# TI_92_power.net
KiCad netlist of a schematic drawn in Altium Designer
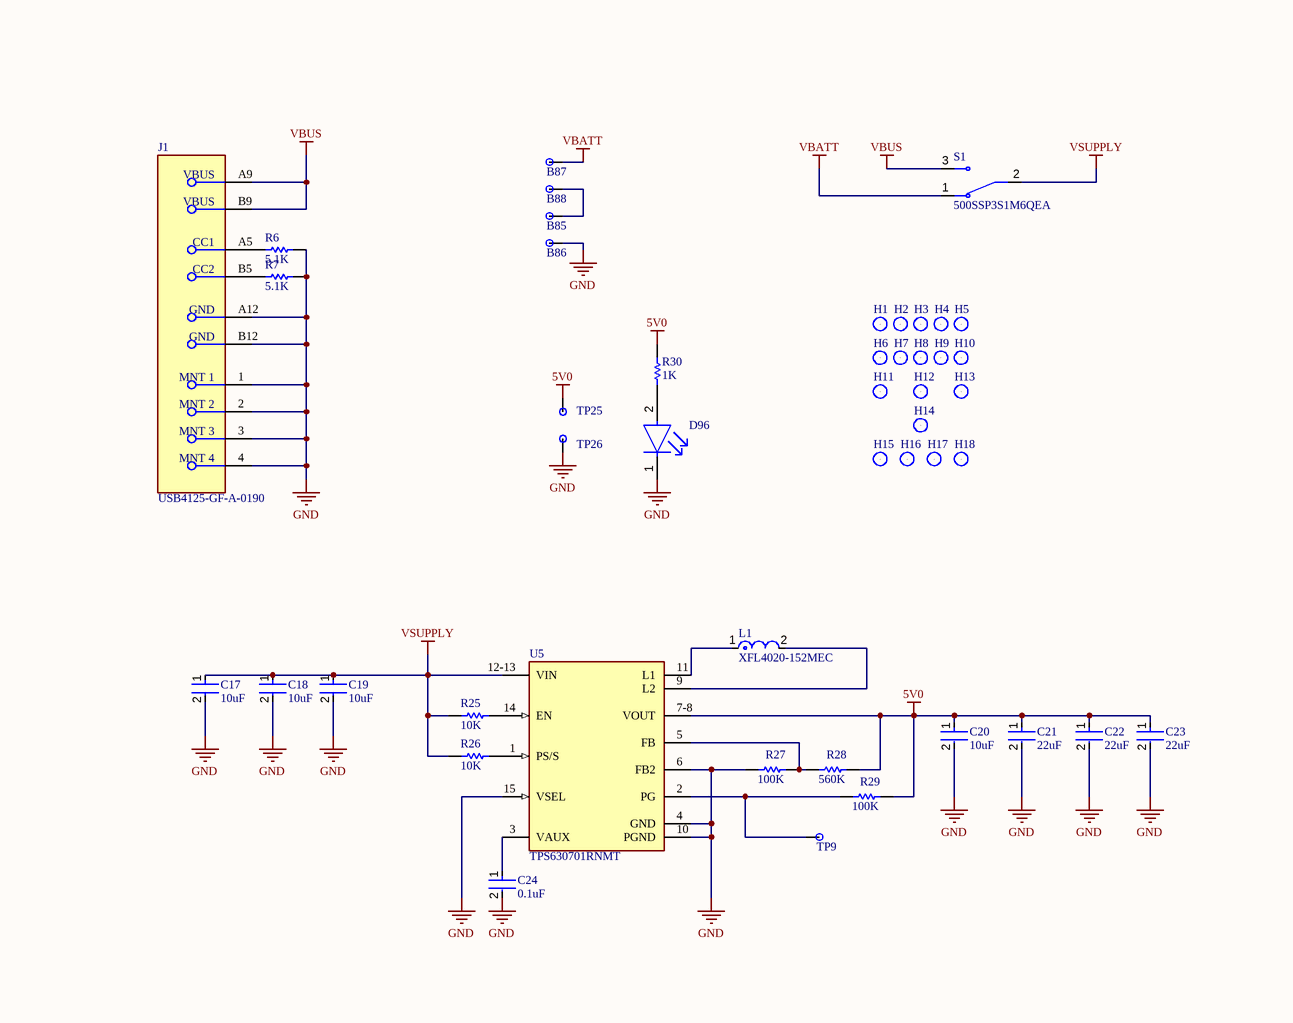
[diagram p0: TI_92_power.SchDoc]

(export (version "E")
  (design (tool "Eeschema 10.0.6"))
  (components
    (comp (ref "B85")
      (value "Test Pad")
      (footprint "10mm_x_10mm_PAD")
      (description "Various Test Pads")
      (libsource (lib "TI_kbd") (part "Test_Pad"))
    )
    (comp (ref "B86")
      (value "Test Pad")
      (footprint "10mm_x_8mm_PAD")
      (description "Various Test Pads")
      (libsource (lib "TI_kbd") (part "Test_Pad"))
    )
    (comp (ref "B87")
      (value "Test Pad")
      (footprint "10mm_x_10mm_PAD")
      (description "Various Test Pads")
      (libsource (lib "TI_kbd") (part "Test_Pad"))
    )
    (comp (ref "B88")
      (value "Test Pad")
      (footprint "10mm_x_8mm_PAD")
      (description "Various Test Pads")
      (libsource (lib "TI_kbd") (part "Test_Pad"))
    )
    (comp (ref "C17")
      (value "10uF")
      (footprint "FP-GRM21B-0_2-e0_2_0_7-IPC_A")
      (description "Chip Multilayer Ceramic Capacitors for General Purpose, 0805, 10uF, X7S, 22%, 20%, 25V")
      (fields (field (name "TOLERANCE") "20%"))
      (libsource (lib "Altium Content Vault") (part "b4654b650e69147ec39a6b967a45e02"))
    )
    (comp (ref "C18")
      (value "10uF")
      (footprint "FP-GRM21B-0_2-e0_2_0_7-IPC_A")
      (description "Chip Multilayer Ceramic Capacitors for General Purpose, 0805, 10uF, X7S, 22%, 20%, 25V")
      (fields (field (name "TOLERANCE") "20%"))
      (libsource (lib "Altium Content Vault") (part "b4654b650e69147ec39a6b967a45e02"))
    )
    (comp (ref "C19")
      (value "10uF")
      (footprint "FP-0603-L_1_6_0_2-W_0_8_0-MFG")
      (description "Multilayer Ceramic Capacitor 10uF 25V X5R 20% SMD 0603 T/R")
      (fields (field (name "TOLERANCE") "20%"))
      (libsource (lib "Altium Content Vault") (part "b4654b650e69147ec39a6b967a45e02"))
    )
    (comp (ref "C20")
      (value "10uF")
      (footprint "FP-0603-L_1_6_0_2-W_0_8_0-MFG")
      (description "Multilayer Ceramic Capacitor 10uF 25V X5R 20% SMD 0603 T/R")
      (fields (field (name "TOLERANCE") "20%"))
      (libsource (lib "Altium Content Vault") (part "b4654b650e69147ec39a6b967a45e02"))
    )
    (comp (ref "C21")
      (value "22uF")
      (footprint "FP-GRM21B-0_2-e0_2_0_7-MFG")
      (description "Chip Multilayer Ceramic Capacitors for General Purpose, 0805, 22uF, X6S, 22%, 20%, 16V")
      (fields (field (name "TOLERANCE") "20%"))
      (libsource (lib "Altium Content Vault") (part "b4654b650e69147ec39a6b967a45e02"))
    )
    (comp (ref "C22")
      (value "22uF")
      (footprint "FP-GRM21B-0_2-e0_2_0_7-MFG")
      (description "Chip Multilayer Ceramic Capacitors for General Purpose, 0805, 22uF, X6S, 22%, 20%, 16V")
      (fields (field (name "TOLERANCE") "20%"))
      (libsource (lib "Altium Content Vault") (part "b4654b650e69147ec39a6b967a45e02"))
    )
    (comp (ref "C23")
      (value "22uF")
      (footprint "FP-GRM21B-0_2-e0_2_0_7-MFG")
      (description "Chip Multilayer Ceramic Capacitors for General Purpose, 0805, 22uF, X6S, 22%, 20%, 16V")
      (fields (field (name "TOLERANCE") "20%"))
      (libsource (lib "Altium Content Vault") (part "b4654b650e69147ec39a6b967a45e02"))
    )
    (comp (ref "C24")
      (value "0.1uF")
      (footprint "FP-0402-L_1_0_0_05-W_0_5-IPC_B")
      (description "None")
      (fields (field (name "TOLERANCE") "20%"))
      (libsource (lib "Altium Content Vault") (part "b4654b650e69147ec39a6b967a45e02"))
    )
    (comp (ref "D96")
      (value "APHHS1005CGCK")
      (footprint "FP-APHHS1005CGCK-MFG")
      (description "LED GREEN CLEAR CHIP SMD")
      (libsource (lib "Altium Content Vault") (part "8706943c75ba83719d021d2fdc84c58"))
    )
    (comp (ref "H1")
      (value "Mounting Hole")
      (footprint "2.7mm_HOLE")
      (description "Various Mounting Holes")
      (libsource (lib "TI_kbd") (part "Mounting_Hole"))
    )
    (comp (ref "H2")
      (value "Mounting Hole")
      (footprint "2.7mm_HOLE")
      (description "Various Mounting Holes")
      (libsource (lib "TI_kbd") (part "Mounting_Hole"))
    )
    (comp (ref "H3")
      (value "Mounting Hole")
      (footprint "1.5mm_hole")
      (description "Various Mounting Holes")
      (libsource (lib "TI_kbd") (part "Mounting_Hole"))
    )
    (comp (ref "H4")
      (value "Mounting Hole")
      (footprint "2.7mm_HOLE")
      (description "Various Mounting Holes")
      (libsource (lib "TI_kbd") (part "Mounting_Hole"))
    )
    (comp (ref "H5")
      (value "Mounting Hole")
      (footprint "2.7mm_HOLE")
      (description "Various Mounting Holes")
      (libsource (lib "TI_kbd") (part "Mounting_Hole"))
    )
    (comp (ref "H6")
      (value "Mounting Hole")
      (footprint "2.7mm_HOLE")
      (description "Various Mounting Holes")
      (libsource (lib "TI_kbd") (part "Mounting_Hole"))
    )
    (comp (ref "H7")
      (value "Mounting Hole")
      (footprint "2.7mm_HOLE")
      (description "Various Mounting Holes")
      (libsource (lib "TI_kbd") (part "Mounting_Hole"))
    )
    (comp (ref "H8")
      (value "Mounting Hole")
      (footprint "2.7mm_HOLE")
      (description "Various Mounting Holes")
      (libsource (lib "TI_kbd") (part "Mounting_Hole"))
    )
    (comp (ref "H9")
      (value "Mounting Hole")
      (footprint "2.7mm_HOLE")
      (description "Various Mounting Holes")
      (libsource (lib "TI_kbd") (part "Mounting_Hole"))
    )
    (comp (ref "H10")
      (value "Mounting Hole")
      (footprint "2.7mm_HOLE")
      (description "Various Mounting Holes")
      (libsource (lib "TI_kbd") (part "Mounting_Hole"))
    )
    (comp (ref "H11")
      (value "Mounting Hole")
      (footprint "2.4mm_HOLE")
      (description "Various Mounting Holes")
      (libsource (lib "TI_kbd") (part "Mounting_Hole"))
    )
    (comp (ref "H12")
      (value "Mounting Hole")
      (footprint "2.4mm_HOLE")
      (description "Various Mounting Holes")
      (libsource (lib "TI_kbd") (part "Mounting_Hole"))
    )
    (comp (ref "H13")
      (value "Mounting Hole")
      (footprint "2.4mm_HOLE")
      (description "Various Mounting Holes")
      (libsource (lib "TI_kbd") (part "Mounting_Hole"))
    )
    (comp (ref "H14")
      (value "Mounting Hole")
      (footprint "1.5mm_hole")
      (description "Various Mounting Holes")
      (libsource (lib "TI_kbd") (part "Mounting_Hole"))
    )
    (comp (ref "H15")
      (value "Mounting Hole")
      (footprint "3.1mm_HOLE")
      (description "Various Mounting Holes")
      (libsource (lib "TI_kbd") (part "Mounting_Hole"))
    )
    (comp (ref "H16")
      (value "Mounting Hole")
      (footprint "3.1mm_HOLE")
      (description "Various Mounting Holes")
      (libsource (lib "TI_kbd") (part "Mounting_Hole"))
    )
    (comp (ref "H17")
      (value "Mounting Hole")
      (footprint "3.1mm_HOLE")
      (description "Various Mounting Holes")
      (libsource (lib "TI_kbd") (part "Mounting_Hole"))
    )
    (comp (ref "H18")
      (value "Mounting Hole")
      (footprint "3.1mm_HOLE")
      (description "Various Mounting Holes")
      (libsource (lib "TI_kbd") (part "Mounting_Hole"))
    )
    (comp (ref "J1")
      (value "USB4125-GF-A-0190")
      (footprint "FP-USB4125-GF-A-0190-MFG")
      (description "CONN RCPT TYPE C 6P SMD RA")
      (libsource (lib "Altium Content Vault") (part "a055484d46e58b234844902c9fd883a"))
    )
    (comp (ref "L1")
      (value "XFL4020-152MEC")
      (footprint "FP-XFL4020-MFG")
      (fields (field (name "TOLERANCE") "20%"))
      (libsource (lib "Altium Content Vault") (part "4cc4b267dca4c8e51f7102f422741d8"))
    )
    (comp (ref "R6")
      (value "5.1K")
      (footprint "RESC1005X40X25NL05T10")
      (fields (field (name "PART NUMBER") "RC0402FR-071KL") (field (name "MANUFACTURER") "Yageo / Phycomp"))
      (libsource (lib "Altium Content Vault") (part "RES"))
    )
    (comp (ref "R7")
      (value "5.1K")
      (footprint "RESC1005X40X25NL05T10")
      (fields (field (name "PART NUMBER") "RC0402FR-071KL") (field (name "MANUFACTURER") "Yageo / Phycomp"))
      (libsource (lib "Altium Content Vault") (part "RES"))
    )
    (comp (ref "R25")
      (value "10K")
      (footprint "RESC1005X40X25NL05T10")
      (fields (field (name "PART NUMBER") "RC0402FR-071KL") (field (name "MANUFACTURER") "Yageo / Phycomp"))
      (libsource (lib "Altium Content Vault") (part "RES"))
    )
    (comp (ref "R26")
      (value "10K")
      (footprint "RESC1005X40X25NL05T10")
      (fields (field (name "PART NUMBER") "RC0402FR-071KL") (field (name "MANUFACTURER") "Yageo / Phycomp"))
      (libsource (lib "Altium Content Vault") (part "RES"))
    )
    (comp (ref "R27")
      (value "100K")
      (footprint "RESC1005X40X25NL05T10")
      (fields (field (name "PART NUMBER") "RC0402FR-071KL") (field (name "MANUFACTURER") "Yageo / Phycomp"))
      (libsource (lib "Altium Content Vault") (part "RES"))
    )
    (comp (ref "R28")
      (value "560K")
      (footprint "RESC1005X40X25NL05T10")
      (fields (field (name "PART NUMBER") "RC0402FR-071KL") (field (name "MANUFACTURER") "Yageo / Phycomp"))
      (libsource (lib "Altium Content Vault") (part "RES"))
    )
    (comp (ref "R29")
      (value "100K")
      (footprint "RESC1005X40X25NL05T10")
      (fields (field (name "PART NUMBER") "RC0402FR-071KL") (field (name "MANUFACTURER") "Yageo / Phycomp"))
      (libsource (lib "Altium Content Vault") (part "RES"))
    )
    (comp (ref "R30")
      (value "1K")
      (footprint "RESC1005X40X25NL05T10")
      (fields (field (name "PART NUMBER") "RC0402FR-071KL") (field (name "MANUFACTURER") "Yageo / Phycomp"))
      (libsource (lib "Altium Content Vault") (part "RES"))
    )
    (comp (ref "S1")
      (value "500SSP3S1M6QEA")
      (footprint "SW_500SSP3S1M6QEA")
      (libsource (lib "500SSP3S1M6QEA") (part "500SSP3S1M6QEA"))
    )
    (comp (ref "TP9")
      (value "Test Pad")
      (footprint "1.5MM_PAD")
      (description "Various Test Pads")
      (libsource (lib "TI_kbd") (part "Test_Pad"))
    )
    (comp (ref "TP25")
      (value "Test Pad")
      (footprint "2.5MM_PAD")
      (description "Various Test Pads")
      (libsource (lib "TI_kbd") (part "Test_Pad"))
    )
    (comp (ref "TP26")
      (value "Test Pad")
      (footprint "2.5MM_PAD")
      (description "Various Test Pads")
      (libsource (lib "TI_kbd") (part "Test_Pad"))
    )
    (comp (ref "U5")
      (value "TPS630701RNMT")
      (footprint "FP-RNM0015A-MFG")
      (description "IC REG BCK BST 5V 2A 15VQFN")
      (libsource (lib "Altium Content Vault") (part "68f092fb8842fb8b42a1c3f5a7ce375"))
    )
  )
  (nets
    (net (code "1") (name "5V0") (class "Default")
      (node (ref "C20") (pin "1") (pinfunction "1_1") (pintype "passive"))
      (node (ref "C21") (pin "1") (pinfunction "1_1") (pintype "passive"))
      (node (ref "C22") (pin "1") (pinfunction "1_1") (pintype "passive"))
      (node (ref "C23") (pin "1") (pinfunction "1_1") (pintype "passive"))
      (node (ref "R28") (pin "2") (pinfunction "2_2") (pintype "passive"))
      (node (ref "R29") (pin "2") (pinfunction "2_2") (pintype "passive"))
      (node (ref "R30") (pin "2") (pinfunction "2_2") (pintype "passive"))
      (node (ref "TP25") (pin "1") (pinfunction "PAD_1") (pintype "passive"))
      (node (ref "U5") (pin "7-8") (pinfunction "VOUT_7-8") (pintype "power_in"))
    )
    (net (code "2") (name "GND") (class "Default")
      (node (ref "B86") (pin "1") (pinfunction "PAD_1") (pintype "passive"))
      (node (ref "C17") (pin "2") (pinfunction "2_2") (pintype "passive"))
      (node (ref "C18") (pin "2") (pinfunction "2_2") (pintype "passive"))
      (node (ref "C19") (pin "2") (pinfunction "2_2") (pintype "passive"))
      (node (ref "C20") (pin "2") (pinfunction "2_2") (pintype "passive"))
      (node (ref "C21") (pin "2") (pinfunction "2_2") (pintype "passive"))
      (node (ref "C22") (pin "2") (pinfunction "2_2") (pintype "passive"))
      (node (ref "C23") (pin "2") (pinfunction "2_2") (pintype "passive"))
      (node (ref "C24") (pin "2") (pinfunction "2_2") (pintype "passive"))
      (node (ref "D96") (pin "1") (pinfunction "C_1") (pintype "passive"))
      (node (ref "J1") (pin "1") (pinfunction "MNT_1_1") (pintype "passive"))
      (node (ref "J1") (pin "2") (pinfunction "MNT_2_2") (pintype "passive"))
      (node (ref "J1") (pin "3") (pinfunction "MNT_3_3") (pintype "passive"))
      (node (ref "J1") (pin "4") (pinfunction "MNT_4_4") (pintype "passive"))
      (node (ref "J1") (pin "A12") (pinfunction "GND_A12") (pintype "passive"))
      (node (ref "J1") (pin "B12") (pinfunction "GND_B12") (pintype "passive"))
      (node (ref "R27") (pin "1") (pinfunction "1_1") (pintype "passive"))
      (node (ref "R6") (pin "1") (pinfunction "1_1") (pintype "passive"))
      (node (ref "R7") (pin "1") (pinfunction "1_1") (pintype "passive"))
      (node (ref "TP26") (pin "1") (pinfunction "PAD_1") (pintype "passive"))
      (node (ref "U5") (pin "10") (pinfunction "PGND_10") (pintype "power_in"))
      (node (ref "U5") (pin "15") (pinfunction "VSEL_15") (pintype "input"))
      (node (ref "U5") (pin "4") (pinfunction "GND_4") (pintype "power_in"))
      (node (ref "U5") (pin "6") (pinfunction "FB2_6") (pintype "passive"))
    )
    (net (code "3") (name "Net-(B85-PAD)") (class "Default")
      (node (ref "B85") (pin "1") (pinfunction "PAD_1") (pintype "passive"))
      (node (ref "B88") (pin "1") (pinfunction "PAD_1") (pintype "passive"))
    )
    (net (code "4") (name "Net-(D96-A)") (class "Default")
      (node (ref "D96") (pin "2") (pinfunction "A_2") (pintype "passive"))
      (node (ref "R30") (pin "1") (pinfunction "1_1") (pintype "passive"))
    )
    (net (code "5") (name "Net-(J1-CC1)") (class "Default")
      (node (ref "J1") (pin "A5") (pinfunction "CC1_A5") (pintype "passive"))
      (node (ref "R6") (pin "2") (pinfunction "2_2") (pintype "passive"))
    )
    (net (code "6") (name "Net-(J1-CC2)") (class "Default")
      (node (ref "J1") (pin "B5") (pinfunction "CC2_B5") (pintype "passive"))
      (node (ref "R7") (pin "2") (pinfunction "2_2") (pintype "passive"))
    )
    (net (code "7") (name "Net-(TP9-PAD)") (class "Default")
      (node (ref "R29") (pin "1") (pinfunction "1_1") (pintype "passive"))
      (node (ref "TP9") (pin "1") (pinfunction "PAD_1") (pintype "passive"))
      (node (ref "U5") (pin "2") (pinfunction "PG_2") (pintype "open_collector"))
    )
    (net (code "8") (name "Net-(U5-EN)") (class "Default")
      (node (ref "R25") (pin "1") (pinfunction "1_1") (pintype "passive"))
      (node (ref "U5") (pin "14") (pinfunction "EN_14") (pintype "input"))
    )
    (net (code "9") (name "Net-(U5-FB)") (class "Default")
      (node (ref "R27") (pin "2") (pinfunction "2_2") (pintype "passive"))
      (node (ref "R28") (pin "1") (pinfunction "1_1") (pintype "passive"))
      (node (ref "U5") (pin "5") (pinfunction "FB_5") (pintype "passive"))
    )
    (net (code "10") (name "Net-(U5-L1)") (class "Default")
      (node (ref "L1") (pin "1") (pinfunction "1_1") (pintype "passive"))
      (node (ref "U5") (pin "11") (pinfunction "L1_11") (pintype "passive"))
    )
    (net (code "11") (name "Net-(U5-L2)") (class "Default")
      (node (ref "L1") (pin "2") (pinfunction "2_2") (pintype "passive"))
      (node (ref "U5") (pin "9") (pinfunction "L2_9") (pintype "passive"))
    )
    (net (code "12") (name "Net-(U5-PS{slash}S)") (class "Default")
      (node (ref "R26") (pin "1") (pinfunction "1_1") (pintype "passive"))
      (node (ref "U5") (pin "1") (pinfunction "PS/S_1") (pintype "input"))
    )
    (net (code "13") (name "Net-(U5-VAUX)") (class "Default")
      (node (ref "C24") (pin "1") (pinfunction "1_1") (pintype "passive"))
      (node (ref "U5") (pin "3") (pinfunction "VAUX_3") (pintype "passive"))
    )
    (net (code "14") (name "VBATT") (class "Default")
      (node (ref "B87") (pin "1") (pinfunction "PAD_1") (pintype "passive"))
      (node (ref "S1") (pin "1") (pinfunction "NC_1") (pintype "passive"))
    )
    (net (code "15") (name "VBUS") (class "Default")
      (node (ref "J1") (pin "A9") (pinfunction "VBUS_A9") (pintype "passive"))
      (node (ref "J1") (pin "B9") (pinfunction "VBUS_B9") (pintype "passive"))
      (node (ref "S1") (pin "3") (pinfunction "NO_3") (pintype "passive"))
    )
    (net (code "16") (name "VSUPPLY") (class "Default")
      (node (ref "C17") (pin "1") (pinfunction "1_1") (pintype "passive"))
      (node (ref "C18") (pin "1") (pinfunction "1_1") (pintype "passive"))
      (node (ref "C19") (pin "1") (pinfunction "1_1") (pintype "passive"))
      (node (ref "R25") (pin "2") (pinfunction "2_2") (pintype "passive"))
      (node (ref "R26") (pin "2") (pinfunction "2_2") (pintype "passive"))
      (node (ref "S1") (pin "2") (pinfunction "COM_2") (pintype "passive"))
      (node (ref "U5") (pin "12-13") (pinfunction "VIN_12-13") (pintype "power_in"))
    )
    (net (code "17") (name "unconnected-(H1-HOLE-Pad1)") (class "Default")
      (node (ref "H1") (pin "1") (pinfunction "HOLE_1") (pintype "passive"))
    )
    (net (code "18") (name "unconnected-(H2-HOLE-Pad1)") (class "Default")
      (node (ref "H2") (pin "1") (pinfunction "HOLE_1") (pintype "passive"))
    )
    (net (code "19") (name "unconnected-(H3-HOLE-Pad1)") (class "Default")
      (node (ref "H3") (pin "1") (pinfunction "HOLE_1") (pintype "passive"))
    )
    (net (code "20") (name "unconnected-(H4-HOLE-Pad1)") (class "Default")
      (node (ref "H4") (pin "1") (pinfunction "HOLE_1") (pintype "passive"))
    )
    (net (code "21") (name "unconnected-(H5-HOLE-Pad1)") (class "Default")
      (node (ref "H5") (pin "1") (pinfunction "HOLE_1") (pintype "passive"))
    )
    (net (code "22") (name "unconnected-(H6-HOLE-Pad1)") (class "Default")
      (node (ref "H6") (pin "1") (pinfunction "HOLE_1") (pintype "passive"))
    )
    (net (code "23") (name "unconnected-(H7-HOLE-Pad1)") (class "Default")
      (node (ref "H7") (pin "1") (pinfunction "HOLE_1") (pintype "passive"))
    )
    (net (code "24") (name "unconnected-(H8-HOLE-Pad1)") (class "Default")
      (node (ref "H8") (pin "1") (pinfunction "HOLE_1") (pintype "passive"))
    )
    (net (code "25") (name "unconnected-(H9-HOLE-Pad1)") (class "Default")
      (node (ref "H9") (pin "1") (pinfunction "HOLE_1") (pintype "passive"))
    )
    (net (code "26") (name "unconnected-(H10-HOLE-Pad1)") (class "Default")
      (node (ref "H10") (pin "1") (pinfunction "HOLE_1") (pintype "passive"))
    )
    (net (code "27") (name "unconnected-(H11-HOLE-Pad1)") (class "Default")
      (node (ref "H11") (pin "1") (pinfunction "HOLE_1") (pintype "passive"))
    )
    (net (code "28") (name "unconnected-(H12-HOLE-Pad1)") (class "Default")
      (node (ref "H12") (pin "1") (pinfunction "HOLE_1") (pintype "passive"))
    )
    (net (code "29") (name "unconnected-(H13-HOLE-Pad1)") (class "Default")
      (node (ref "H13") (pin "1") (pinfunction "HOLE_1") (pintype "passive"))
    )
    (net (code "30") (name "unconnected-(H14-HOLE-Pad1)") (class "Default")
      (node (ref "H14") (pin "1") (pinfunction "HOLE_1") (pintype "passive"))
    )
    (net (code "31") (name "unconnected-(H15-HOLE-Pad1)") (class "Default")
      (node (ref "H15") (pin "1") (pinfunction "HOLE_1") (pintype "passive"))
    )
    (net (code "32") (name "unconnected-(H16-HOLE-Pad1)") (class "Default")
      (node (ref "H16") (pin "1") (pinfunction "HOLE_1") (pintype "passive"))
    )
    (net (code "33") (name "unconnected-(H17-HOLE-Pad1)") (class "Default")
      (node (ref "H17") (pin "1") (pinfunction "HOLE_1") (pintype "passive"))
    )
    (net (code "34") (name "unconnected-(H18-HOLE-Pad1)") (class "Default")
      (node (ref "H18") (pin "1") (pinfunction "HOLE_1") (pintype "passive"))
    )
  )
)
